# Transmit.net
KiCad netlist of a schematic drawn in Altium Designer
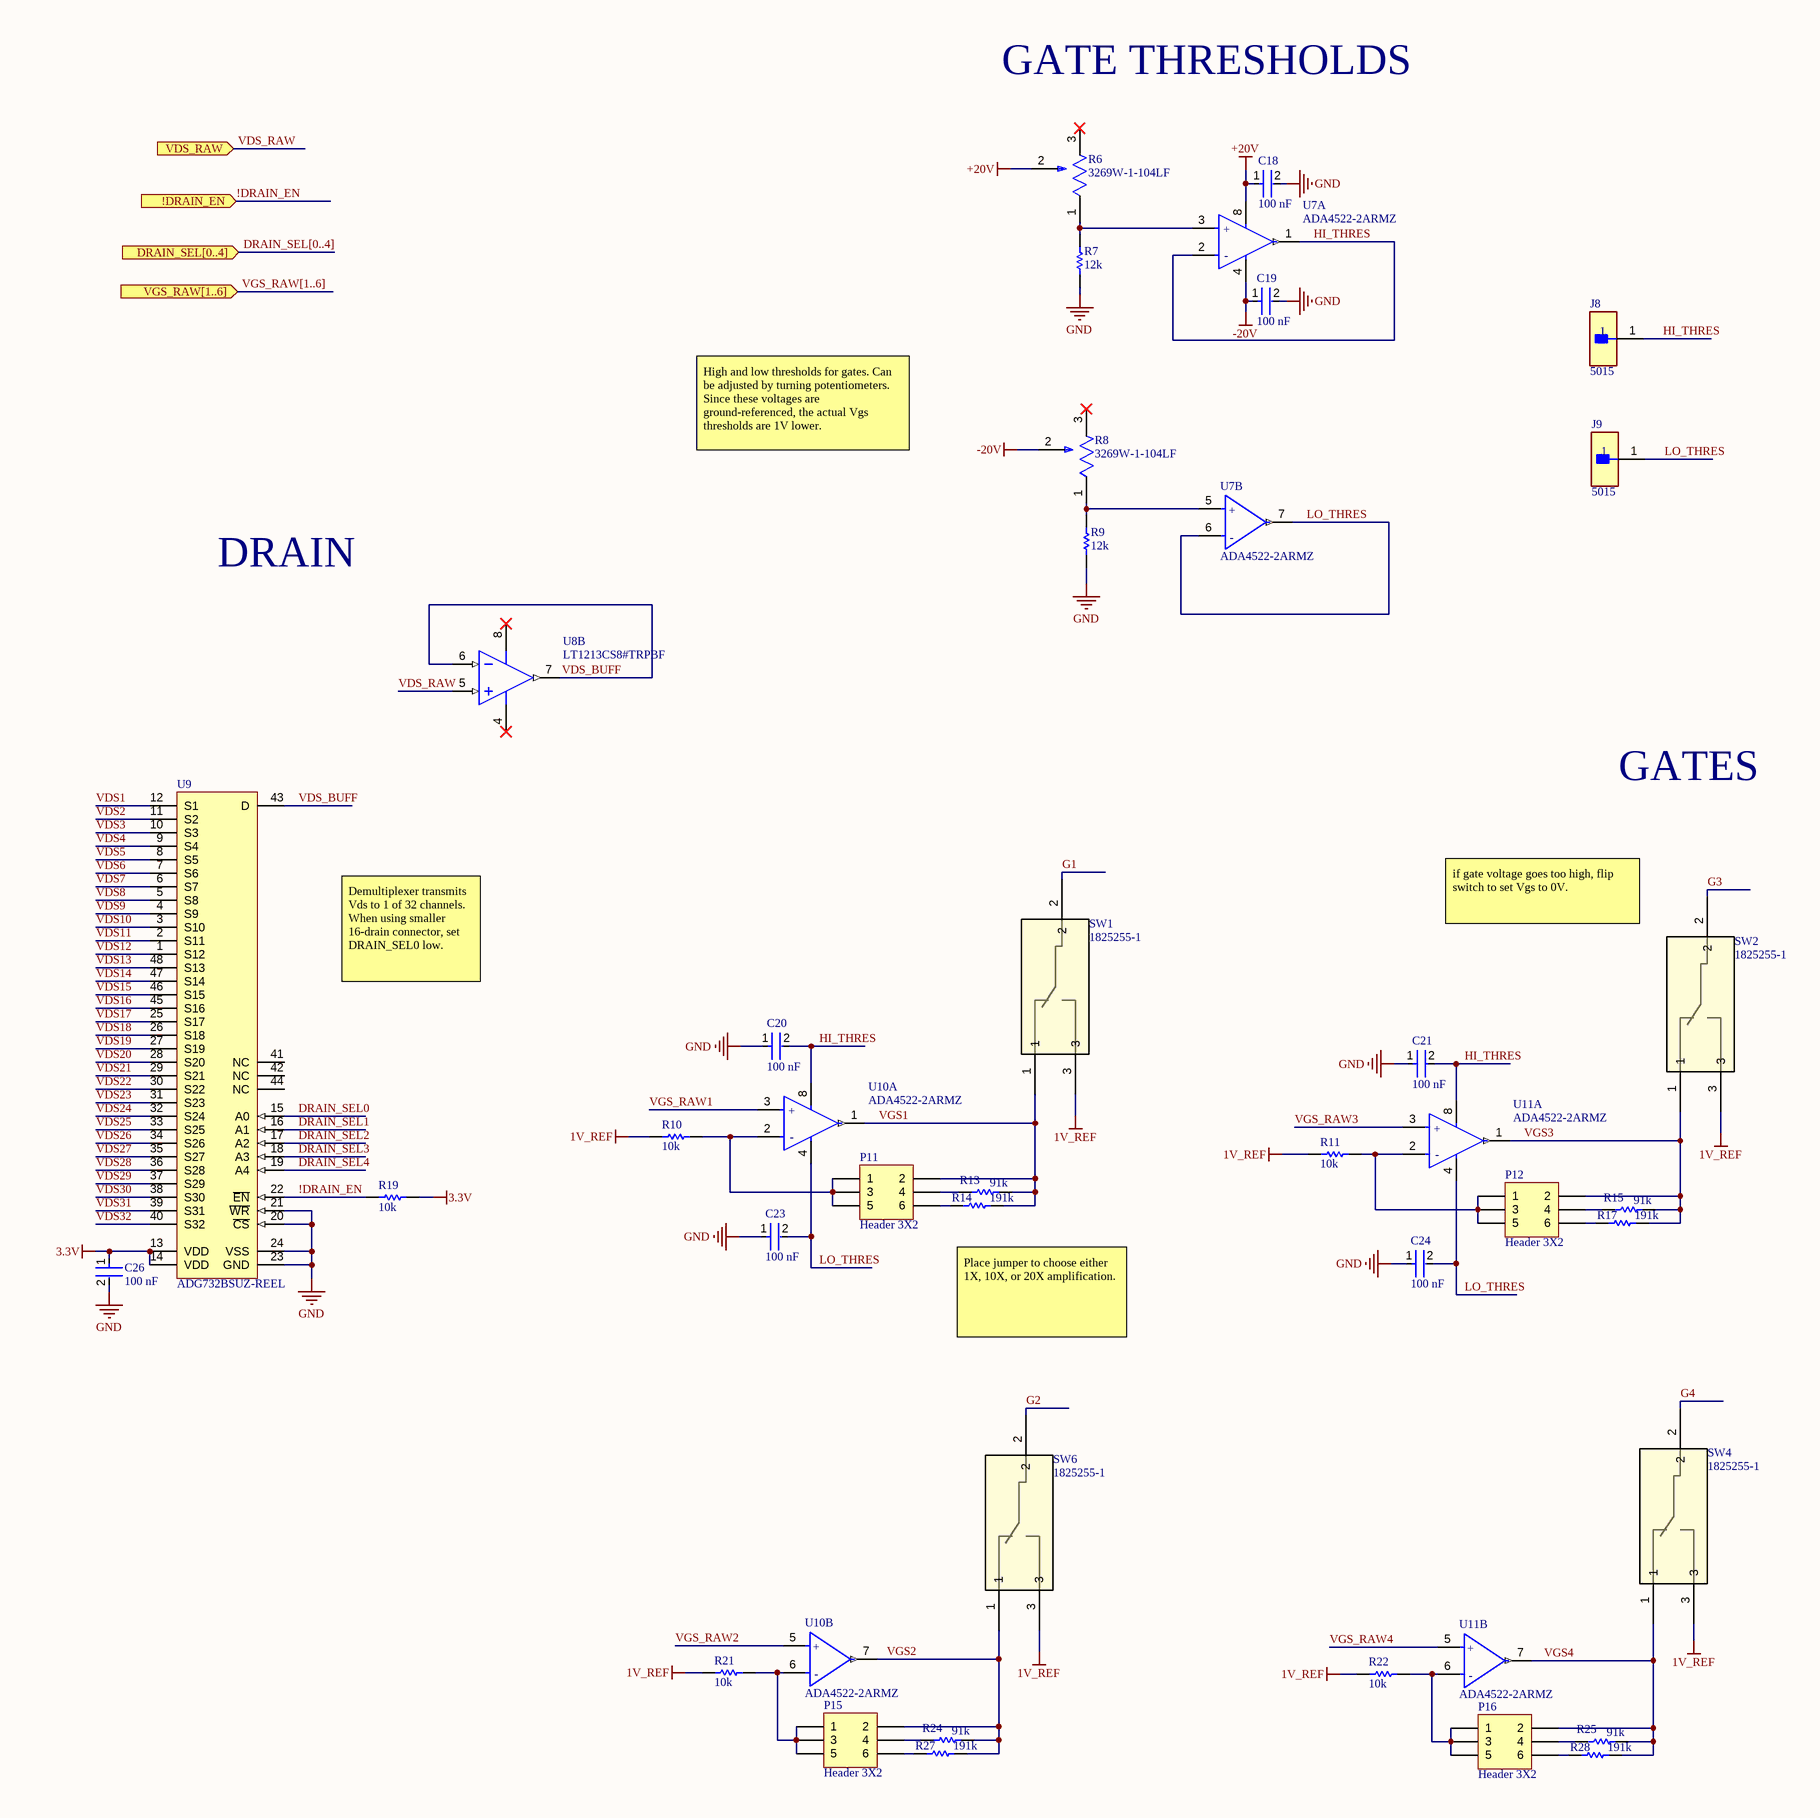
[diagram p0: Transmit.SchDoc, left]
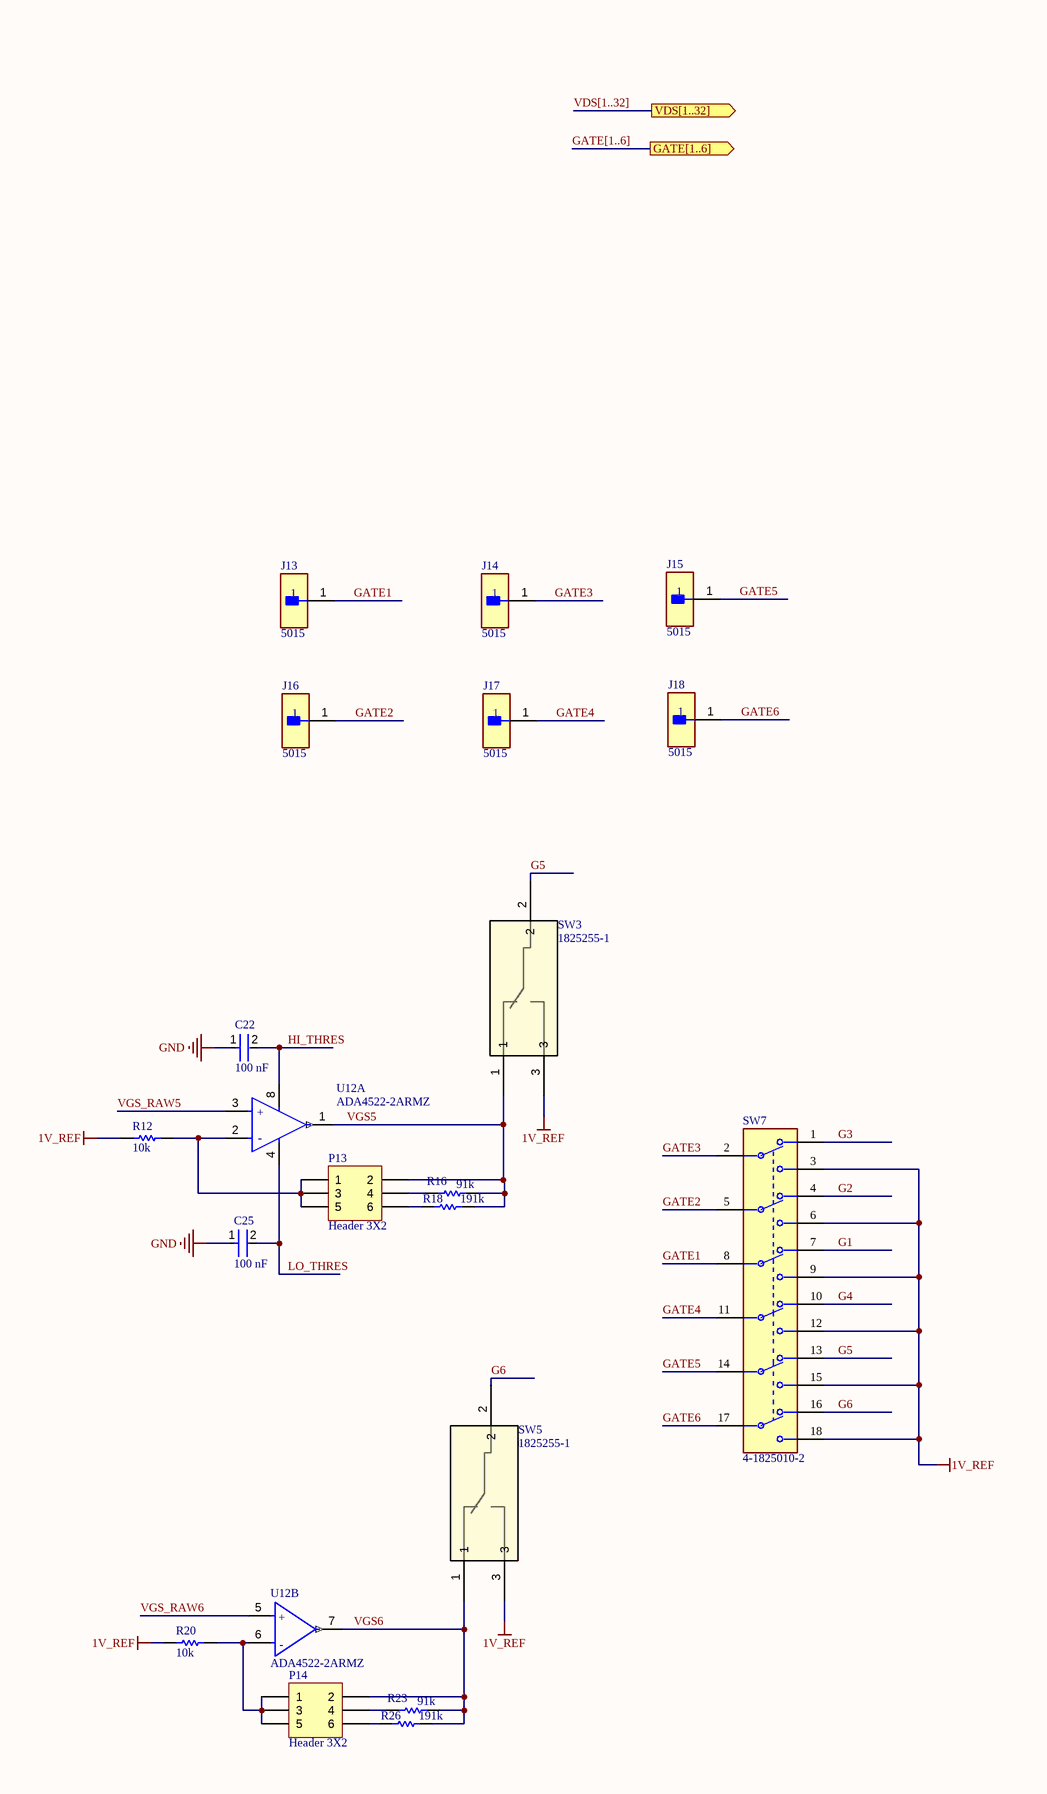
[diagram p1: Transmit.SchDoc, right]

(export (version "E")
  (design (tool "Eeschema 10.0.6"))
  (components
    (comp (ref "C18")
      (value "100 nF")
      (footprint "FP-C0805C-DN-MFG")
      (description "CAP CER 0.1UF 50V X7R 0805")
      (fields
        (field (name "MANUFACTURER PART NUMBER") "C0805C104K5RACTU")
        (field (name "MANUFACTURER") "KEMET")
      )
      (libsource (lib "Altium Content Vault") (part "b4654b650e69147ec39a6b967a45e02"))
    )
    (comp (ref "C19")
      (value "100 nF")
      (footprint "FP-C0805C-DN-MFG")
      (description "CAP CER 0.1UF 50V X7R 0805")
      (fields
        (field (name "MANUFACTURER PART NUMBER") "C0805C104K5RACTU")
        (field (name "MANUFACTURER") "KEMET")
      )
      (libsource (lib "Altium Content Vault") (part "b4654b650e69147ec39a6b967a45e02"))
    )
    (comp (ref "C20")
      (value "100 nF")
      (footprint "FP-C0805C-DN-MFG")
      (description "CAP CER 0.1UF 50V X7R 0805")
      (fields
        (field (name "MANUFACTURER PART NUMBER") "C0805C104K5RACTU")
        (field (name "MANUFACTURER") "KEMET")
      )
      (libsource (lib "Altium Content Vault") (part "b4654b650e69147ec39a6b967a45e02"))
    )
    (comp (ref "C21")
      (value "100 nF")
      (footprint "FP-C0805C-DN-MFG")
      (description "CAP CER 0.1UF 50V X7R 0805")
      (fields
        (field (name "MANUFACTURER PART NUMBER") "C0805C104K5RACTU")
        (field (name "MANUFACTURER") "KEMET")
      )
      (libsource (lib "Altium Content Vault") (part "b4654b650e69147ec39a6b967a45e02"))
    )
    (comp (ref "C22")
      (value "100 nF")
      (footprint "FP-C0805C-DN-MFG")
      (description "CAP CER 0.1UF 50V X7R 0805")
      (fields
        (field (name "MANUFACTURER PART NUMBER") "C0805C104K5RACTU")
        (field (name "MANUFACTURER") "KEMET")
      )
      (libsource (lib "Altium Content Vault") (part "b4654b650e69147ec39a6b967a45e02"))
    )
    (comp (ref "C23")
      (value "100 nF")
      (footprint "FP-C0805C-DN-MFG")
      (description "CAP CER 0.1UF 50V X7R 0805")
      (fields
        (field (name "MANUFACTURER PART NUMBER") "C0805C104K5RACTU")
        (field (name "MANUFACTURER") "KEMET")
      )
      (libsource (lib "Altium Content Vault") (part "b4654b650e69147ec39a6b967a45e02"))
    )
    (comp (ref "C24")
      (value "100 nF")
      (footprint "FP-C0805C-DN-MFG")
      (description "CAP CER 0.1UF 50V X7R 0805")
      (fields
        (field (name "MANUFACTURER PART NUMBER") "C0805C104K5RACTU")
        (field (name "MANUFACTURER") "KEMET")
      )
      (libsource (lib "Altium Content Vault") (part "b4654b650e69147ec39a6b967a45e02"))
    )
    (comp (ref "C25")
      (value "100 nF")
      (footprint "FP-C0805C-DN-MFG")
      (description "CAP CER 0.1UF 50V X7R 0805")
      (fields
        (field (name "MANUFACTURER PART NUMBER") "C0805C104K5RACTU")
        (field (name "MANUFACTURER") "KEMET")
      )
      (libsource (lib "Altium Content Vault") (part "b4654b650e69147ec39a6b967a45e02"))
    )
    (comp (ref "C26")
      (value "100 nF")
      (footprint "FP-C0805C-DN-MFG")
      (description "CAP CER 0.1UF 50V X7R 0805")
      (fields
        (field (name "MANUFACTURER PART NUMBER") "C0805C104K5RACTU")
        (field (name "MANUFACTURER") "KEMET")
      )
      (libsource (lib "Altium Content Vault") (part "b4654b650e69147ec39a6b967a45e02"))
    )
    (comp (ref "J8")
      (value "5015")
      (footprint "FP-5015-MFG")
      (description "PC TEST POINT MINIATURE")
      (fields
        (field (name "MANUFACTURER") "keystone")
        (field (name "OCTOPART") "https://octopart.com/5015-keystone-3822")
      )
      (libsource (lib "Altium Content Vault") (part "dd45045ce8184df9e99e12baf3f412c"))
    )
    (comp (ref "J9")
      (value "5015")
      (footprint "FP-5015-MFG")
      (description "PC TEST POINT MINIATURE")
      (fields
        (field (name "MANUFACTURER") "keystone")
        (field (name "OCTOPART") "https://octopart.com/5015-keystone-3822")
      )
      (libsource (lib "Altium Content Vault") (part "dd45045ce8184df9e99e12baf3f412c"))
    )
    (comp (ref "J13")
      (value "5015")
      (footprint "FP-5015-MFG")
      (description "PC TEST POINT MINIATURE")
      (fields
        (field (name "MANUFACTURER") "keystone")
        (field (name "OCTOPART") "https://octopart.com/5015-keystone-3822")
      )
      (libsource (lib "Altium Content Vault") (part "dd45045ce8184df9e99e12baf3f412c"))
    )
    (comp (ref "J14")
      (value "5015")
      (footprint "FP-5015-MFG")
      (description "PC TEST POINT MINIATURE")
      (fields
        (field (name "MANUFACTURER") "keystone")
        (field (name "OCTOPART") "https://octopart.com/5015-keystone-3822")
      )
      (libsource (lib "Altium Content Vault") (part "dd45045ce8184df9e99e12baf3f412c"))
    )
    (comp (ref "J15")
      (value "5015")
      (footprint "FP-5015-MFG")
      (description "PC TEST POINT MINIATURE")
      (fields
        (field (name "MANUFACTURER") "keystone")
        (field (name "OCTOPART") "https://octopart.com/5015-keystone-3822")
      )
      (libsource (lib "Altium Content Vault") (part "dd45045ce8184df9e99e12baf3f412c"))
    )
    (comp (ref "J16")
      (value "5015")
      (footprint "FP-5015-MFG")
      (description "PC TEST POINT MINIATURE")
      (fields
        (field (name "MANUFACTURER") "keystone")
        (field (name "OCTOPART") "https://octopart.com/5015-keystone-3822")
      )
      (libsource (lib "Altium Content Vault") (part "dd45045ce8184df9e99e12baf3f412c"))
    )
    (comp (ref "J17")
      (value "5015")
      (footprint "FP-5015-MFG")
      (description "PC TEST POINT MINIATURE")
      (fields
        (field (name "MANUFACTURER") "keystone")
        (field (name "OCTOPART") "https://octopart.com/5015-keystone-3822")
      )
      (libsource (lib "Altium Content Vault") (part "dd45045ce8184df9e99e12baf3f412c"))
    )
    (comp (ref "J18")
      (value "5015")
      (footprint "FP-5015-MFG")
      (description "PC TEST POINT MINIATURE")
      (fields
        (field (name "MANUFACTURER") "keystone")
        (field (name "OCTOPART") "https://octopart.com/5015-keystone-3822")
      )
      (libsource (lib "Altium Content Vault") (part "dd45045ce8184df9e99e12baf3f412c"))
    )
    (comp (ref "P11")
      (value "Header 3X2")
      (footprint "HDR2X3")
      (description "Header, 3-Pin, Dual row")
      (fields (field (name "PUBLISHER") "Altium Limited"))
      (libsource (lib "Miscellaneous Connectors") (part "Header 3X2"))
    )
    (comp (ref "P12")
      (value "Header 3X2")
      (footprint "HDR2X3")
      (description "Header, 3-Pin, Dual row")
      (fields (field (name "PUBLISHER") "Altium Limited"))
      (libsource (lib "Miscellaneous Connectors") (part "Header 3X2"))
    )
    (comp (ref "P13")
      (value "Header 3X2")
      (footprint "HDR2X3")
      (description "Header, 3-Pin, Dual row")
      (fields (field (name "PUBLISHER") "Altium Limited"))
      (libsource (lib "Miscellaneous Connectors") (part "Header 3X2"))
    )
    (comp (ref "P14")
      (value "Header 3X2")
      (footprint "HDR2X3")
      (description "Header, 3-Pin, Dual row")
      (fields (field (name "PUBLISHER") "Altium Limited"))
      (libsource (lib "Miscellaneous Connectors") (part "Header 3X2"))
    )
    (comp (ref "P15")
      (value "Header 3X2")
      (footprint "HDR2X3")
      (description "Header, 3-Pin, Dual row")
      (fields (field (name "PUBLISHER") "Altium Limited"))
      (libsource (lib "Miscellaneous Connectors") (part "Header 3X2"))
    )
    (comp (ref "P16")
      (value "Header 3X2")
      (footprint "HDR2X3")
      (description "Header, 3-Pin, Dual row")
      (fields (field (name "PUBLISHER") "Altium Limited"))
      (libsource (lib "Miscellaneous Connectors") (part "Header 3X2"))
    )
    (comp (ref "R6")
      (value "3269W-1-104LF")
      (footprint "FP-3269W-MFG")
      (description "TRIMMER 100K OHM 0.25W SMD")
      (fields (field (name "MANUFACTURER") "Bourns") (field (name "TOLERANCE") "10%"))
      (libsource (lib "Altium Content Vault") (part "e2bd51d327feade59aab0772042b0d4"))
    )
    (comp (ref "R7")
      (value "12k")
      (footprint "RESC2013X60X40ML20T25")
      (fields (field (name "PART NUMBER") "ERA6AEB123V") (field (name "MANUFACTURER") "Panasonic"))
      (libsource (lib "Altium Content Vault") (part "RES"))
    )
    (comp (ref "R8")
      (value "3269W-1-104LF")
      (footprint "FP-3269W-MFG")
      (description "TRIMMER 100K OHM 0.25W SMD")
      (fields (field (name "MANUFACTURER") "Bourns") (field (name "TOLERANCE") "10%"))
      (libsource (lib "Altium Content Vault") (part "e2bd51d327feade59aab0772042b0d4"))
    )
    (comp (ref "R9")
      (value "12k")
      (footprint "RESC2013X60X40ML20T25")
      (fields (field (name "PART NUMBER") "ERA6AEB123V") (field (name "MANUFACTURER") "Panasonic"))
      (libsource (lib "Altium Content Vault") (part "RES"))
    )
    (comp (ref "R10")
      (value "10k")
      (footprint "RESC2013X60X35NL10T20")
      (description "Chip Resistor, 10 KOhm, +/- 1%, 0.125 W, -55 to 155 degC, 0805 (2012 Metric), RoHS, Tape and Reel")
      (fields (field (name "MANUFACTURER") "Yageo"))
      (libsource (lib "Altium Content Vault") (part "RES-2"))
    )
    (comp (ref "R11")
      (value "10k")
      (footprint "RESC2013X60X35NL10T20")
      (description "Chip Resistor, 10 KOhm, +/- 1%, 0.125 W, -55 to 155 degC, 0805 (2012 Metric), RoHS, Tape and Reel")
      (fields (field (name "MANUFACTURER") "Yageo"))
      (libsource (lib "Altium Content Vault") (part "RES-2"))
    )
    (comp (ref "R12")
      (value "10k")
      (footprint "RESC2013X60X35NL10T20")
      (description "Chip Resistor, 10 KOhm, +/- 1%, 0.125 W, -55 to 155 degC, 0805 (2012 Metric), RoHS, Tape and Reel")
      (fields (field (name "MANUFACTURER") "Yageo"))
      (libsource (lib "Altium Content Vault") (part "RES-2"))
    )
    (comp (ref "R13")
      (value "91k")
      (footprint "RESC2013X60X40LL20T25")
      (fields (field (name "PART NUMBER") "ERA6AEB913V") (field (name "MANUFACTURER") "Panasonic"))
      (libsource (lib "Altium Content Vault") (part "RES"))
    )
    (comp (ref "R14")
      (value "191k")
      (footprint "RESC2013X70X40ML20T20")
      (fields (field (name "MANUFACTURER") "Panasonic") (field (name "PART NUMBER") "ERJ-6ENF1913V"))
      (libsource (lib "Altium Content Vault") (part "RES"))
    )
    (comp (ref "R15")
      (value "91k")
      (footprint "RESC2013X60X40LL20T25")
      (fields (field (name "PART NUMBER") "ERA6AEB913V") (field (name "MANUFACTURER") "Panasonic"))
      (libsource (lib "Altium Content Vault") (part "RES"))
    )
    (comp (ref "R16")
      (value "91k")
      (footprint "RESC2013X60X40LL20T25")
      (fields (field (name "PART NUMBER") "ERA6AEB913V") (field (name "MANUFACTURER") "Panasonic"))
      (libsource (lib "Altium Content Vault") (part "RES"))
    )
    (comp (ref "R17")
      (value "191k")
      (footprint "RESC2013X70X40ML20T20")
      (fields (field (name "MANUFACTURER") "Panasonic") (field (name "PART NUMBER") "ERJ-6ENF1913V"))
      (libsource (lib "Altium Content Vault") (part "RES"))
    )
    (comp (ref "R18")
      (value "191k")
      (footprint "RESC2013X70X40ML20T20")
      (fields (field (name "MANUFACTURER") "Panasonic") (field (name "PART NUMBER") "ERJ-6ENF1913V"))
      (libsource (lib "Altium Content Vault") (part "RES"))
    )
    (comp (ref "R19")
      (value "10k")
      (footprint "RESC2013X60X35NL10T20")
      (description "Chip Resistor, 10 KOhm, +/- 1%, 0.125 W, -55 to 155 degC, 0805 (2012 Metric), RoHS, Tape and Reel")
      (fields (field (name "MANUFACTURER") "Yageo"))
      (libsource (lib "Altium Content Vault") (part "RES-2"))
    )
    (comp (ref "R20")
      (value "10k")
      (footprint "RESC2013X60X35NL10T20")
      (description "Chip Resistor, 10 KOhm, +/- 1%, 0.125 W, -55 to 155 degC, 0805 (2012 Metric), RoHS, Tape and Reel")
      (fields (field (name "MANUFACTURER") "Yageo"))
      (libsource (lib "Altium Content Vault") (part "RES-2"))
    )
    (comp (ref "R21")
      (value "10k")
      (footprint "RESC2013X60X35NL10T20")
      (description "Chip Resistor, 10 KOhm, +/- 1%, 0.125 W, -55 to 155 degC, 0805 (2012 Metric), RoHS, Tape and Reel")
      (fields (field (name "MANUFACTURER") "Yageo"))
      (libsource (lib "Altium Content Vault") (part "RES-2"))
    )
    (comp (ref "R22")
      (value "10k")
      (footprint "RESC2013X60X35NL10T20")
      (description "Chip Resistor, 10 KOhm, +/- 1%, 0.125 W, -55 to 155 degC, 0805 (2012 Metric), RoHS, Tape and Reel")
      (fields (field (name "MANUFACTURER") "Yageo"))
      (libsource (lib "Altium Content Vault") (part "RES-2"))
    )
    (comp (ref "R23")
      (value "91k")
      (footprint "RESC2013X60X40LL20T25")
      (fields (field (name "PART NUMBER") "ERA6AEB913V") (field (name "MANUFACTURER") "Panasonic"))
      (libsource (lib "Altium Content Vault") (part "RES"))
    )
    (comp (ref "R24")
      (value "91k")
      (footprint "RESC2013X60X40LL20T25")
      (fields (field (name "PART NUMBER") "ERA6AEB913V") (field (name "MANUFACTURER") "Panasonic"))
      (libsource (lib "Altium Content Vault") (part "RES"))
    )
    (comp (ref "R25")
      (value "91k")
      (footprint "RESC2013X60X40LL20T25")
      (fields (field (name "PART NUMBER") "ERA6AEB913V") (field (name "MANUFACTURER") "Panasonic"))
      (libsource (lib "Altium Content Vault") (part "RES"))
    )
    (comp (ref "R26")
      (value "191k")
      (footprint "RESC2013X70X40ML20T20")
      (fields (field (name "MANUFACTURER") "Panasonic") (field (name "PART NUMBER") "ERJ-6ENF1913V"))
      (libsource (lib "Altium Content Vault") (part "RES"))
    )
    (comp (ref "R27")
      (value "191k")
      (footprint "RESC2013X70X40ML20T20")
      (fields (field (name "MANUFACTURER") "Panasonic") (field (name "PART NUMBER") "ERJ-6ENF1913V"))
      (libsource (lib "Altium Content Vault") (part "RES"))
    )
    (comp (ref "R28")
      (value "191k")
      (footprint "RESC2013X70X40ML20T20")
      (fields (field (name "MANUFACTURER") "Panasonic") (field (name "PART NUMBER") "ERJ-6ENF1913V"))
      (libsource (lib "Altium Content Vault") (part "RES"))
    )
    (comp (ref "SW1")
      (value "1825255-1")
      (footprint "SW3_1825255-1_TEC")
      (description "No Description Available")
      (fields (field (name "COPYRIGHT") "Copyright (C) 2022 Ultra Librarian. All rights reserved."))
      (libsource (lib "1825255-1") (part "1825255-1"))
    )
    (comp (ref "SW2")
      (value "1825255-1")
      (footprint "SW3_1825255-1_TEC")
      (description "No Description Available")
      (fields (field (name "COPYRIGHT") "Copyright (C) 2022 Ultra Librarian. All rights reserved."))
      (libsource (lib "1825255-1") (part "1825255-1"))
    )
    (comp (ref "SW3")
      (value "1825255-1")
      (footprint "SW3_1825255-1_TEC")
      (description "No Description Available")
      (fields (field (name "COPYRIGHT") "Copyright (C) 2022 Ultra Librarian. All rights reserved."))
      (libsource (lib "1825255-1") (part "1825255-1"))
    )
    (comp (ref "SW4")
      (value "1825255-1")
      (footprint "SW3_1825255-1_TEC")
      (description "No Description Available")
      (fields (field (name "COPYRIGHT") "Copyright (C) 2022 Ultra Librarian. All rights reserved."))
      (libsource (lib "1825255-1") (part "1825255-1"))
    )
    (comp (ref "SW5")
      (value "1825255-1")
      (footprint "SW3_1825255-1_TEC")
      (description "No Description Available")
      (fields (field (name "COPYRIGHT") "Copyright (C) 2022 Ultra Librarian. All rights reserved."))
      (libsource (lib "1825255-1") (part "1825255-1"))
    )
    (comp (ref "SW6")
      (value "1825255-1")
      (footprint "SW3_1825255-1_TEC")
      (description "No Description Available")
      (fields (field (name "COPYRIGHT") "Copyright (C) 2022 Ultra Librarian. All rights reserved."))
      (libsource (lib "1825255-1") (part "1825255-1"))
    )
    (comp (ref "SW7")
      (value "4-1825010-2")
      (footprint "FP-4-1825010-2-MFG")
      (description "SWITCH SLIDE 6PDT 300MA 115V")
      (libsource (lib "Altium Content Vault") (part "3b30da29821d25944dadded3e2f277e"))
    )
    (comp (ref "U7")
      (value "ADA4522-2ARMZ")
      (footprint "FP-RM-8-IPC_C")
      (description "IC OPAMP ZERO-DRIFT 2 CIRC 8MSOP")
      (libsource (lib "Altium Content Vault") (part "e8c52d48d03680a0ba04c611cf3b55d"))
    )
    (comp (ref "U8")
      (value "LT1213CS8#TRPBF")
      (footprint "LT-S8-8_N")
      (fields
        (field (name "LINEAR TECHNOLOGY PART NUMBER") "LT1213")
        (field (name "MANUFACTURER") "Linear Technology")
      )
      (libsource (lib "Altium Content Vault") (part "LT-LT1364-LT18XX-8"))
    )
    (comp (ref "U9")
      (value "ADG732BSUZ-REEL")
      (footprint "ADI-SU-48_N")
      (fields (field (name "MANUFACTURER") "Analog Devices"))
      (libsource (lib "Altium Content Vault") (part "ADI-ADG732-SU-48"))
    )
    (comp (ref "U10")
      (value "ADA4522-2ARMZ")
      (footprint "FP-RM-8-IPC_C")
      (description "IC OPAMP ZERO-DRIFT 2 CIRC 8MSOP")
      (libsource (lib "Altium Content Vault") (part "e8c52d48d03680a0ba04c611cf3b55d"))
    )
    (comp (ref "U11")
      (value "ADA4522-2ARMZ")
      (footprint "FP-RM-8-IPC_C")
      (description "IC OPAMP ZERO-DRIFT 2 CIRC 8MSOP")
      (libsource (lib "Altium Content Vault") (part "e8c52d48d03680a0ba04c611cf3b55d"))
    )
    (comp (ref "U12")
      (value "ADA4522-2ARMZ")
      (footprint "FP-RM-8-IPC_C")
      (description "IC OPAMP ZERO-DRIFT 2 CIRC 8MSOP")
      (libsource (lib "Altium Content Vault") (part "e8c52d48d03680a0ba04c611cf3b55d"))
    )
  )
  (nets
    (net (code "1") (name "+20V") (class "Default")
      (node (ref "C18") (pin "1") (pinfunction "1_1") (pintype "passive"))
      (node (ref "R6") (pin "2") (pinfunction "WIPER_2") (pintype "passive"))
      (node (ref "U7") (pin "8") (pinfunction "V+_8") (pintype "power_in"))
    )
    (net (code "2") (name "-20V") (class "Default")
      (node (ref "C19") (pin "1") (pinfunction "1_1") (pintype "passive"))
      (node (ref "R8") (pin "2") (pinfunction "WIPER_2") (pintype "passive"))
      (node (ref "U7") (pin "4") (pinfunction "V-_4") (pintype "power_in"))
    )
    (net (code "3") (name "/!DRAIN_EN") (class "Default")
      (node (ref "R19") (pin "2") (pinfunction "2_2") (pintype "passive"))
      (node (ref "U9") (pin "22") (pinfunction "~{EN}_22") (pintype "input"))
    )
    (net (code "4") (name "/DRAIN_SEL0") (class "Default")
      (node (ref "U9") (pin "15") (pinfunction "A0_15") (pintype "input"))
    )
    (net (code "5") (name "/DRAIN_SEL1") (class "Default")
      (node (ref "U9") (pin "16") (pinfunction "A1_16") (pintype "input"))
    )
    (net (code "6") (name "/DRAIN_SEL2") (class "Default")
      (node (ref "U9") (pin "17") (pinfunction "A2_17") (pintype "input"))
    )
    (net (code "7") (name "/DRAIN_SEL3") (class "Default")
      (node (ref "U9") (pin "18") (pinfunction "A3_18") (pintype "input"))
    )
    (net (code "8") (name "/DRAIN_SEL4") (class "Default")
      (node (ref "U9") (pin "19") (pinfunction "A4_19") (pintype "input"))
    )
    (net (code "10") (name "/G1") (class "Default")
      (node (ref "SW1") (pin "2") (pinfunction "2_2") (pintype "passive"))
      (node (ref "SW7") (pin "7") (pinfunction "7_7") (pintype "passive"))
    )
    (net (code "11") (name "/G2") (class "Default")
      (node (ref "SW6") (pin "2") (pinfunction "2_2") (pintype "passive"))
      (node (ref "SW7") (pin "4") (pinfunction "4_4") (pintype "passive"))
    )
    (net (code "12") (name "/G3") (class "Default")
      (node (ref "SW2") (pin "2") (pinfunction "2_2") (pintype "passive"))
      (node (ref "SW7") (pin "1") (pinfunction "1_1") (pintype "passive"))
    )
    (net (code "13") (name "/G4") (class "Default")
      (node (ref "SW4") (pin "2") (pinfunction "2_2") (pintype "passive"))
      (node (ref "SW7") (pin "10") (pinfunction "10_10") (pintype "passive"))
    )
    (net (code "14") (name "/G5") (class "Default")
      (node (ref "SW3") (pin "2") (pinfunction "2_2") (pintype "passive"))
      (node (ref "SW7") (pin "13") (pinfunction "13_13") (pintype "passive"))
    )
    (net (code "15") (name "/G6") (class "Default")
      (node (ref "SW5") (pin "2") (pinfunction "2_2") (pintype "passive"))
      (node (ref "SW7") (pin "16") (pinfunction "16_16") (pintype "passive"))
    )
    (net (code "16") (name "/GATE1") (class "Default")
      (node (ref "J13") (pin "1") (pinfunction "1_1") (pintype "passive"))
      (node (ref "SW7") (pin "8") (pinfunction "8_8") (pintype "passive"))
    )
    (net (code "17") (name "/GATE2") (class "Default")
      (node (ref "J16") (pin "1") (pinfunction "1_1") (pintype "passive"))
      (node (ref "SW7") (pin "5") (pinfunction "5_5") (pintype "passive"))
    )
    (net (code "18") (name "/GATE3") (class "Default")
      (node (ref "J14") (pin "1") (pinfunction "1_1") (pintype "passive"))
      (node (ref "SW7") (pin "2") (pinfunction "2_2") (pintype "passive"))
    )
    (net (code "19") (name "/GATE4") (class "Default")
      (node (ref "J17") (pin "1") (pinfunction "1_1") (pintype "passive"))
      (node (ref "SW7") (pin "11") (pinfunction "11_11") (pintype "passive"))
    )
    (net (code "20") (name "/GATE5") (class "Default")
      (node (ref "J15") (pin "1") (pinfunction "1_1") (pintype "passive"))
      (node (ref "SW7") (pin "14") (pinfunction "14_14") (pintype "passive"))
    )
    (net (code "21") (name "/GATE6") (class "Default")
      (node (ref "J18") (pin "1") (pinfunction "1_1") (pintype "passive"))
      (node (ref "SW7") (pin "17") (pinfunction "17_17") (pintype "passive"))
    )
    (net (code "23") (name "/HI_THRES") (class "Default")
      (node (ref "C20") (pin "2") (pinfunction "2_2") (pintype "passive"))
      (node (ref "C21") (pin "2") (pinfunction "2_2") (pintype "passive"))
      (node (ref "C22") (pin "2") (pinfunction "2_2") (pintype "passive"))
      (node (ref "J8") (pin "1") (pinfunction "1_1") (pintype "passive"))
      (node (ref "U10") (pin "8") (pinfunction "V+_8") (pintype "power_in"))
      (node (ref "U11") (pin "8") (pinfunction "V+_8") (pintype "power_in"))
      (node (ref "U12") (pin "8") (pinfunction "V+_8") (pintype "power_in"))
      (node (ref "U7") (pin "1") (pinfunction "OUT_A_1") (pintype "output"))
      (node (ref "U7") (pin "2") (pinfunction "-IN_A_2") (pintype "tri_state"))
    )
    (net (code "24") (name "/LO_THRES") (class "Default")
      (node (ref "C23") (pin "2") (pinfunction "2_2") (pintype "passive"))
      (node (ref "C24") (pin "2") (pinfunction "2_2") (pintype "passive"))
      (node (ref "C25") (pin "2") (pinfunction "2_2") (pintype "passive"))
      (node (ref "J9") (pin "1") (pinfunction "1_1") (pintype "passive"))
      (node (ref "U10") (pin "4") (pinfunction "V-_4") (pintype "power_in"))
      (node (ref "U11") (pin "4") (pinfunction "V-_4") (pintype "power_in"))
      (node (ref "U12") (pin "4") (pinfunction "V-_4") (pintype "power_in"))
      (node (ref "U7") (pin "6") (pinfunction "-IN_B_6") (pintype "tri_state"))
      (node (ref "U7") (pin "7") (pinfunction "OUT_B_7") (pintype "output"))
    )
    (net (code "25") (name "/VDS1") (class "Default")
      (node (ref "U9") (pin "12") (pinfunction "S1_12") (pintype "passive"))
    )
    (net (code "26") (name "/VDS2") (class "Default")
      (node (ref "U9") (pin "11") (pinfunction "S2_11") (pintype "passive"))
    )
    (net (code "27") (name "/VDS3") (class "Default")
      (node (ref "U9") (pin "10") (pinfunction "S3_10") (pintype "passive"))
    )
    (net (code "28") (name "/VDS4") (class "Default")
      (node (ref "U9") (pin "9") (pinfunction "S4_9") (pintype "passive"))
    )
    (net (code "29") (name "/VDS5") (class "Default")
      (node (ref "U9") (pin "8") (pinfunction "S5_8") (pintype "passive"))
    )
    (net (code "30") (name "/VDS6") (class "Default")
      (node (ref "U9") (pin "7") (pinfunction "S6_7") (pintype "passive"))
    )
    (net (code "31") (name "/VDS7") (class "Default")
      (node (ref "U9") (pin "6") (pinfunction "S7_6") (pintype "passive"))
    )
    (net (code "32") (name "/VDS8") (class "Default")
      (node (ref "U9") (pin "5") (pinfunction "S8_5") (pintype "passive"))
    )
    (net (code "33") (name "/VDS9") (class "Default")
      (node (ref "U9") (pin "4") (pinfunction "S9_4") (pintype "passive"))
    )
    (net (code "34") (name "/VDS10") (class "Default")
      (node (ref "U9") (pin "3") (pinfunction "S10_3") (pintype "passive"))
    )
    (net (code "35") (name "/VDS11") (class "Default")
      (node (ref "U9") (pin "2") (pinfunction "S11_2") (pintype "passive"))
    )
    (net (code "36") (name "/VDS12") (class "Default")
      (node (ref "U9") (pin "1") (pinfunction "S12_1") (pintype "passive"))
    )
    (net (code "37") (name "/VDS13") (class "Default")
      (node (ref "U9") (pin "48") (pinfunction "S13_48") (pintype "passive"))
    )
    (net (code "38") (name "/VDS14") (class "Default")
      (node (ref "U9") (pin "47") (pinfunction "S14_47") (pintype "passive"))
    )
    (net (code "39") (name "/VDS15") (class "Default")
      (node (ref "U9") (pin "46") (pinfunction "S15_46") (pintype "passive"))
    )
    (net (code "40") (name "/VDS16") (class "Default")
      (node (ref "U9") (pin "45") (pinfunction "S16_45") (pintype "passive"))
    )
    (net (code "41") (name "/VDS17") (class "Default")
      (node (ref "U9") (pin "25") (pinfunction "S17_25") (pintype "passive"))
    )
    (net (code "42") (name "/VDS18") (class "Default")
      (node (ref "U9") (pin "26") (pinfunction "S18_26") (pintype "passive"))
    )
    (net (code "43") (name "/VDS19") (class "Default")
      (node (ref "U9") (pin "27") (pinfunction "S19_27") (pintype "passive"))
    )
    (net (code "44") (name "/VDS20") (class "Default")
      (node (ref "U9") (pin "28") (pinfunction "S20_28") (pintype "passive"))
    )
    (net (code "45") (name "/VDS21") (class "Default")
      (node (ref "U9") (pin "29") (pinfunction "S21_29") (pintype "passive"))
    )
    (net (code "46") (name "/VDS22") (class "Default")
      (node (ref "U9") (pin "30") (pinfunction "S22_30") (pintype "passive"))
    )
    (net (code "47") (name "/VDS23") (class "Default")
      (node (ref "U9") (pin "31") (pinfunction "S23_31") (pintype "passive"))
    )
    (net (code "48") (name "/VDS24") (class "Default")
      (node (ref "U9") (pin "32") (pinfunction "S24_32") (pintype "passive"))
    )
    (net (code "49") (name "/VDS25") (class "Default")
      (node (ref "U9") (pin "33") (pinfunction "S25_33") (pintype "passive"))
    )
    (net (code "50") (name "/VDS26") (class "Default")
      (node (ref "U9") (pin "34") (pinfunction "S26_34") (pintype "passive"))
    )
    (net (code "51") (name "/VDS27") (class "Default")
      (node (ref "U9") (pin "35") (pinfunction "S27_35") (pintype "passive"))
    )
    (net (code "52") (name "/VDS28") (class "Default")
      (node (ref "U9") (pin "36") (pinfunction "S28_36") (pintype "passive"))
    )
    (net (code "53") (name "/VDS29") (class "Default")
      (node (ref "U9") (pin "37") (pinfunction "S29_37") (pintype "passive"))
    )
    (net (code "54") (name "/VDS30") (class "Default")
      (node (ref "U9") (pin "38") (pinfunction "S30_38") (pintype "passive"))
    )
    (net (code "55") (name "/VDS31") (class "Default")
      (node (ref "U9") (pin "39") (pinfunction "S31_39") (pintype "passive"))
    )
    (net (code "56") (name "/VDS32") (class "Default")
      (node (ref "U9") (pin "40") (pinfunction "S32_40") (pintype "passive"))
    )
    (net (code "58") (name "/VDS_BUFF") (class "Default")
      (node (ref "U8") (pin "6") (pinfunction "-IN_B_6") (pintype "input"))
      (node (ref "U8") (pin "7") (pinfunction "OUT_B_7") (pintype "output"))
      (node (ref "U9") (pin "43") (pinfunction "D_43") (pintype "passive"))
    )
    (net (code "59") (name "/VDS_RAW") (class "Default")
      (node (ref "U8") (pin "5") (pinfunction "+IN_B_5") (pintype "input"))
    )
    (net (code "60") (name "/VGS1") (class "Default")
      (node (ref "P11") (pin "2") (pinfunction "2_2") (pintype "passive"))
      (node (ref "R13") (pin "2") (pinfunction "2_2") (pintype "passive"))
      (node (ref "R14") (pin "2") (pinfunction "2_2") (pintype "passive"))
      (node (ref "SW1") (pin "1") (pinfunction "1_1") (pintype "passive"))
      (node (ref "U10") (pin "1") (pinfunction "OUT_A_1") (pintype "output"))
    )
    (net (code "61") (name "/VGS2") (class "Default")
      (node (ref "P15") (pin "2") (pinfunction "2_2") (pintype "passive"))
      (node (ref "R24") (pin "2") (pinfunction "2_2") (pintype "passive"))
      (node (ref "R27") (pin "2") (pinfunction "2_2") (pintype "passive"))
      (node (ref "SW6") (pin "1") (pinfunction "1_1") (pintype "passive"))
      (node (ref "U10") (pin "7") (pinfunction "OUT_B_7") (pintype "output"))
    )
    (net (code "62") (name "/VGS3") (class "Default")
      (node (ref "P12") (pin "2") (pinfunction "2_2") (pintype "passive"))
      (node (ref "R15") (pin "2") (pinfunction "2_2") (pintype "passive"))
      (node (ref "R17") (pin "2") (pinfunction "2_2") (pintype "passive"))
      (node (ref "SW2") (pin "1") (pinfunction "1_1") (pintype "passive"))
      (node (ref "U11") (pin "1") (pinfunction "OUT_A_1") (pintype "output"))
    )
    (net (code "63") (name "/VGS4") (class "Default")
      (node (ref "P16") (pin "2") (pinfunction "2_2") (pintype "passive"))
      (node (ref "R25") (pin "2") (pinfunction "2_2") (pintype "passive"))
      (node (ref "R28") (pin "2") (pinfunction "2_2") (pintype "passive"))
      (node (ref "SW4") (pin "1") (pinfunction "1_1") (pintype "passive"))
      (node (ref "U11") (pin "7") (pinfunction "OUT_B_7") (pintype "output"))
    )
    (net (code "64") (name "/VGS5") (class "Default")
      (node (ref "P13") (pin "2") (pinfunction "2_2") (pintype "passive"))
      (node (ref "R16") (pin "2") (pinfunction "2_2") (pintype "passive"))
      (node (ref "R18") (pin "2") (pinfunction "2_2") (pintype "passive"))
      (node (ref "SW3") (pin "1") (pinfunction "1_1") (pintype "passive"))
      (node (ref "U12") (pin "1") (pinfunction "OUT_A_1") (pintype "output"))
    )
    (net (code "65") (name "/VGS6") (class "Default")
      (node (ref "P14") (pin "2") (pinfunction "2_2") (pintype "passive"))
      (node (ref "R23") (pin "2") (pinfunction "2_2") (pintype "passive"))
      (node (ref "R26") (pin "2") (pinfunction "2_2") (pintype "passive"))
      (node (ref "SW5") (pin "1") (pinfunction "1_1") (pintype "passive"))
      (node (ref "U12") (pin "7") (pinfunction "OUT_B_7") (pintype "output"))
    )
    (net (code "66") (name "/VGS_RAW1") (class "Default")
      (node (ref "U10") (pin "3") (pinfunction "+IN_A_3") (pintype "tri_state"))
    )
    (net (code "67") (name "/VGS_RAW2") (class "Default")
      (node (ref "U10") (pin "5") (pinfunction "+IN_B_5") (pintype "tri_state"))
    )
    (net (code "68") (name "/VGS_RAW3") (class "Default")
      (node (ref "U11") (pin "3") (pinfunction "+IN_A_3") (pintype "tri_state"))
    )
    (net (code "69") (name "/VGS_RAW4") (class "Default")
      (node (ref "U11") (pin "5") (pinfunction "+IN_B_5") (pintype "tri_state"))
    )
    (net (code "70") (name "/VGS_RAW5") (class "Default")
      (node (ref "U12") (pin "3") (pinfunction "+IN_A_3") (pintype "tri_state"))
    )
    (net (code "71") (name "/VGS_RAW6") (class "Default")
      (node (ref "U12") (pin "5") (pinfunction "+IN_B_5") (pintype "tri_state"))
    )
    (net (code "73") (name "1V_REF") (class "Default")
      (node (ref "R10") (pin "2") (pinfunction "2_2") (pintype "passive"))
      (node (ref "R11") (pin "2") (pinfunction "2_2") (pintype "passive"))
      (node (ref "R12") (pin "2") (pinfunction "2_2") (pintype "passive"))
      (node (ref "R20") (pin "2") (pinfunction "2_2") (pintype "passive"))
      (node (ref "R21") (pin "2") (pinfunction "2_2") (pintype "passive"))
      (node (ref "R22") (pin "2") (pinfunction "2_2") (pintype "passive"))
      (node (ref "SW1") (pin "3") (pinfunction "3_3") (pintype "passive"))
      (node (ref "SW2") (pin "3") (pinfunction "3_3") (pintype "passive"))
      (node (ref "SW3") (pin "3") (pinfunction "3_3") (pintype "passive"))
      (node (ref "SW4") (pin "3") (pinfunction "3_3") (pintype "passive"))
      (node (ref "SW5") (pin "3") (pinfunction "3_3") (pintype "passive"))
      (node (ref "SW6") (pin "3") (pinfunction "3_3") (pintype "passive"))
      (node (ref "SW7") (pin "12") (pinfunction "12_12") (pintype "passive"))
      (node (ref "SW7") (pin "15") (pinfunction "15_15") (pintype "passive"))
      (node (ref "SW7") (pin "18") (pinfunction "18_18") (pintype "passive"))
      (node (ref "SW7") (pin "3") (pinfunction "3_3") (pintype "passive"))
      (node (ref "SW7") (pin "6") (pinfunction "6_6") (pintype "passive"))
      (node (ref "SW7") (pin "9") (pinfunction "9_9") (pintype "passive"))
    )
    (net (code "74") (name "3.3V") (class "Default")
      (node (ref "C26") (pin "1") (pinfunction "1_1") (pintype "passive"))
      (node (ref "R19") (pin "1") (pinfunction "1_1") (pintype "passive"))
      (node (ref "U9") (pin "13") (pinfunction "VDD_13") (pintype "power_in"))
      (node (ref "U9") (pin "14") (pinfunction "VDD_14") (pintype "power_in"))
    )
    (net (code "75") (name "GND") (class "Default")
      (node (ref "C18") (pin "2") (pinfunction "2_2") (pintype "passive"))
      (node (ref "C19") (pin "2") (pinfunction "2_2") (pintype "passive"))
      (node (ref "C20") (pin "1") (pinfunction "1_1") (pintype "passive"))
      (node (ref "C21") (pin "1") (pinfunction "1_1") (pintype "passive"))
      (node (ref "C22") (pin "1") (pinfunction "1_1") (pintype "passive"))
      (node (ref "C23") (pin "1") (pinfunction "1_1") (pintype "passive"))
      (node (ref "C24") (pin "1") (pinfunction "1_1") (pintype "passive"))
      (node (ref "C25") (pin "1") (pinfunction "1_1") (pintype "passive"))
      (node (ref "C26") (pin "2") (pinfunction "2_2") (pintype "passive"))
      (node (ref "R7") (pin "1") (pinfunction "1_1") (pintype "passive"))
      (node (ref "R9") (pin "1") (pinfunction "1_1") (pintype "passive"))
      (node (ref "U9") (pin "20") (pinfunction "~{CS}_20") (pintype "input"))
      (node (ref "U9") (pin "21") (pinfunction "~{WR}_21") (pintype "input"))
      (node (ref "U9") (pin "23") (pinfunction "GND_23") (pintype "power_in"))
      (node (ref "U9") (pin "24") (pinfunction "VSS_24") (pintype "power_in"))
    )
    (net (code "76") (name "Net-(P11-Pad4)") (class "Default")
      (node (ref "P11") (pin "4") (pinfunction "4_4") (pintype "passive"))
      (node (ref "R13") (pin "1") (pinfunction "1_1") (pintype "passive"))
    )
    (net (code "77") (name "Net-(P11-Pad6)") (class "Default")
      (node (ref "P11") (pin "6") (pinfunction "6_6") (pintype "passive"))
      (node (ref "R14") (pin "1") (pinfunction "1_1") (pintype "passive"))
    )
    (net (code "78") (name "Net-(P12-Pad4)") (class "Default")
      (node (ref "P12") (pin "4") (pinfunction "4_4") (pintype "passive"))
      (node (ref "R15") (pin "1") (pinfunction "1_1") (pintype "passive"))
    )
    (net (code "79") (name "Net-(P12-Pad6)") (class "Default")
      (node (ref "P12") (pin "6") (pinfunction "6_6") (pintype "passive"))
      (node (ref "R17") (pin "1") (pinfunction "1_1") (pintype "passive"))
    )
    (net (code "80") (name "Net-(P13-Pad4)") (class "Default")
      (node (ref "P13") (pin "4") (pinfunction "4_4") (pintype "passive"))
      (node (ref "R16") (pin "1") (pinfunction "1_1") (pintype "passive"))
    )
    (net (code "81") (name "Net-(P13-Pad6)") (class "Default")
      (node (ref "P13") (pin "6") (pinfunction "6_6") (pintype "passive"))
      (node (ref "R18") (pin "1") (pinfunction "1_1") (pintype "passive"))
    )
    (net (code "82") (name "Net-(P14-Pad4)") (class "Default")
      (node (ref "P14") (pin "4") (pinfunction "4_4") (pintype "passive"))
      (node (ref "R23") (pin "1") (pinfunction "1_1") (pintype "passive"))
    )
    (net (code "83") (name "Net-(P14-Pad6)") (class "Default")
      (node (ref "P14") (pin "6") (pinfunction "6_6") (pintype "passive"))
      (node (ref "R26") (pin "1") (pinfunction "1_1") (pintype "passive"))
    )
    (net (code "84") (name "Net-(P15-Pad4)") (class "Default")
      (node (ref "P15") (pin "4") (pinfunction "4_4") (pintype "passive"))
      (node (ref "R24") (pin "1") (pinfunction "1_1") (pintype "passive"))
    )
    (net (code "85") (name "Net-(P15-Pad6)") (class "Default")
      (node (ref "P15") (pin "6") (pinfunction "6_6") (pintype "passive"))
      (node (ref "R27") (pin "1") (pinfunction "1_1") (pintype "passive"))
    )
    (net (code "86") (name "Net-(P16-Pad4)") (class "Default")
      (node (ref "P16") (pin "4") (pinfunction "4_4") (pintype "passive"))
      (node (ref "R25") (pin "1") (pinfunction "1_1") (pintype "passive"))
    )
    (net (code "87") (name "Net-(P16-Pad6)") (class "Default")
      (node (ref "P16") (pin "6") (pinfunction "6_6") (pintype "passive"))
      (node (ref "R28") (pin "1") (pinfunction "1_1") (pintype "passive"))
    )
    (net (code "88") (name "Net-(R6-CCW)") (class "Default")
      (node (ref "R6") (pin "1") (pinfunction "CCW_1") (pintype "passive"))
      (node (ref "R7") (pin "2") (pinfunction "2_2") (pintype "passive"))
      (node (ref "U7") (pin "3") (pinfunction "+IN_A_3") (pintype "tri_state"))
    )
    (net (code "89") (name "Net-(R8-CCW)") (class "Default")
      (node (ref "R8") (pin "1") (pinfunction "CCW_1") (pintype "passive"))
      (node (ref "R9") (pin "2") (pinfunction "2_2") (pintype "passive"))
      (node (ref "U7") (pin "5") (pinfunction "+IN_B_5") (pintype "tri_state"))
    )
    (net (code "90") (name "Net-(U10A--IN_A)") (class "Default")
      (node (ref "P11") (pin "1") (pinfunction "1_1") (pintype "passive"))
      (node (ref "P11") (pin "3") (pinfunction "3_3") (pintype "passive"))
      (node (ref "P11") (pin "5") (pinfunction "5_5") (pintype "passive"))
      (node (ref "R10") (pin "1") (pinfunction "1_1") (pintype "passive"))
      (node (ref "U10") (pin "2") (pinfunction "-IN_A_2") (pintype "tri_state"))
    )
    (net (code "91") (name "Net-(U10B--IN_B)") (class "Default")
      (node (ref "P15") (pin "1") (pinfunction "1_1") (pintype "passive"))
      (node (ref "P15") (pin "3") (pinfunction "3_3") (pintype "passive"))
      (node (ref "P15") (pin "5") (pinfunction "5_5") (pintype "passive"))
      (node (ref "R21") (pin "1") (pinfunction "1_1") (pintype "passive"))
      (node (ref "U10") (pin "6") (pinfunction "-IN_B_6") (pintype "tri_state"))
    )
    (net (code "92") (name "Net-(U11A--IN_A)") (class "Default")
      (node (ref "P12") (pin "1") (pinfunction "1_1") (pintype "passive"))
      (node (ref "P12") (pin "3") (pinfunction "3_3") (pintype "passive"))
      (node (ref "P12") (pin "5") (pinfunction "5_5") (pintype "passive"))
      (node (ref "R11") (pin "1") (pinfunction "1_1") (pintype "passive"))
      (node (ref "U11") (pin "2") (pinfunction "-IN_A_2") (pintype "tri_state"))
    )
    (net (code "93") (name "Net-(U11B--IN_B)") (class "Default")
      (node (ref "P16") (pin "1") (pinfunction "1_1") (pintype "passive"))
      (node (ref "P16") (pin "3") (pinfunction "3_3") (pintype "passive"))
      (node (ref "P16") (pin "5") (pinfunction "5_5") (pintype "passive"))
      (node (ref "R22") (pin "1") (pinfunction "1_1") (pintype "passive"))
      (node (ref "U11") (pin "6") (pinfunction "-IN_B_6") (pintype "tri_state"))
    )
    (net (code "94") (name "Net-(U12A--IN_A)") (class "Default")
      (node (ref "P13") (pin "1") (pinfunction "1_1") (pintype "passive"))
      (node (ref "P13") (pin "3") (pinfunction "3_3") (pintype "passive"))
      (node (ref "P13") (pin "5") (pinfunction "5_5") (pintype "passive"))
      (node (ref "R12") (pin "1") (pinfunction "1_1") (pintype "passive"))
      (node (ref "U12") (pin "2") (pinfunction "-IN_A_2") (pintype "tri_state"))
    )
    (net (code "95") (name "Net-(U12B--IN_B)") (class "Default")
      (node (ref "P14") (pin "1") (pinfunction "1_1") (pintype "passive"))
      (node (ref "P14") (pin "3") (pinfunction "3_3") (pintype "passive"))
      (node (ref "P14") (pin "5") (pinfunction "5_5") (pintype "passive"))
      (node (ref "R20") (pin "1") (pinfunction "1_1") (pintype "passive"))
      (node (ref "U12") (pin "6") (pinfunction "-IN_B_6") (pintype "tri_state"))
    )
    (net (code "96") (name "unconnected-(R6-CW-Pad3)") (class "Default")
      (node (ref "R6") (pin "3") (pinfunction "CW_3") (pintype "passive+no_connect"))
    )
    (net (code "97") (name "unconnected-(R8-CW-Pad3)") (class "Default")
      (node (ref "R8") (pin "3") (pinfunction "CW_3") (pintype "passive+no_connect"))
    )
    (net (code "98") (name "unconnected-(U8B-V+-Pad8)") (class "Default")
      (node (ref "U8") (pin "8") (pinfunction "V+_8") (pintype "power_in+no_connect"))
    )
    (net (code "99") (name "unconnected-(U8B-V--Pad4)") (class "Default")
      (node (ref "U8") (pin "4") (pinfunction "V-_4") (pintype "power_in+no_connect"))
    )
    (net (code "100") (name "unconnected-(U9-NC-Pad41)") (class "Default")
      (node (ref "U9") (pin "41") (pinfunction "NC_41") (pintype "passive"))
    )
    (net (code "101") (name "unconnected-(U9-NC-Pad42)") (class "Default")
      (node (ref "U9") (pin "42") (pinfunction "NC_42") (pintype "passive"))
    )
    (net (code "102") (name "unconnected-(U9-NC-Pad44)") (class "Default")
      (node (ref "U9") (pin "44") (pinfunction "NC_44") (pintype "passive"))
    )
  )
)
